# linear_supply2.net
KiCad netlist of a schematic drawn in EAGLE
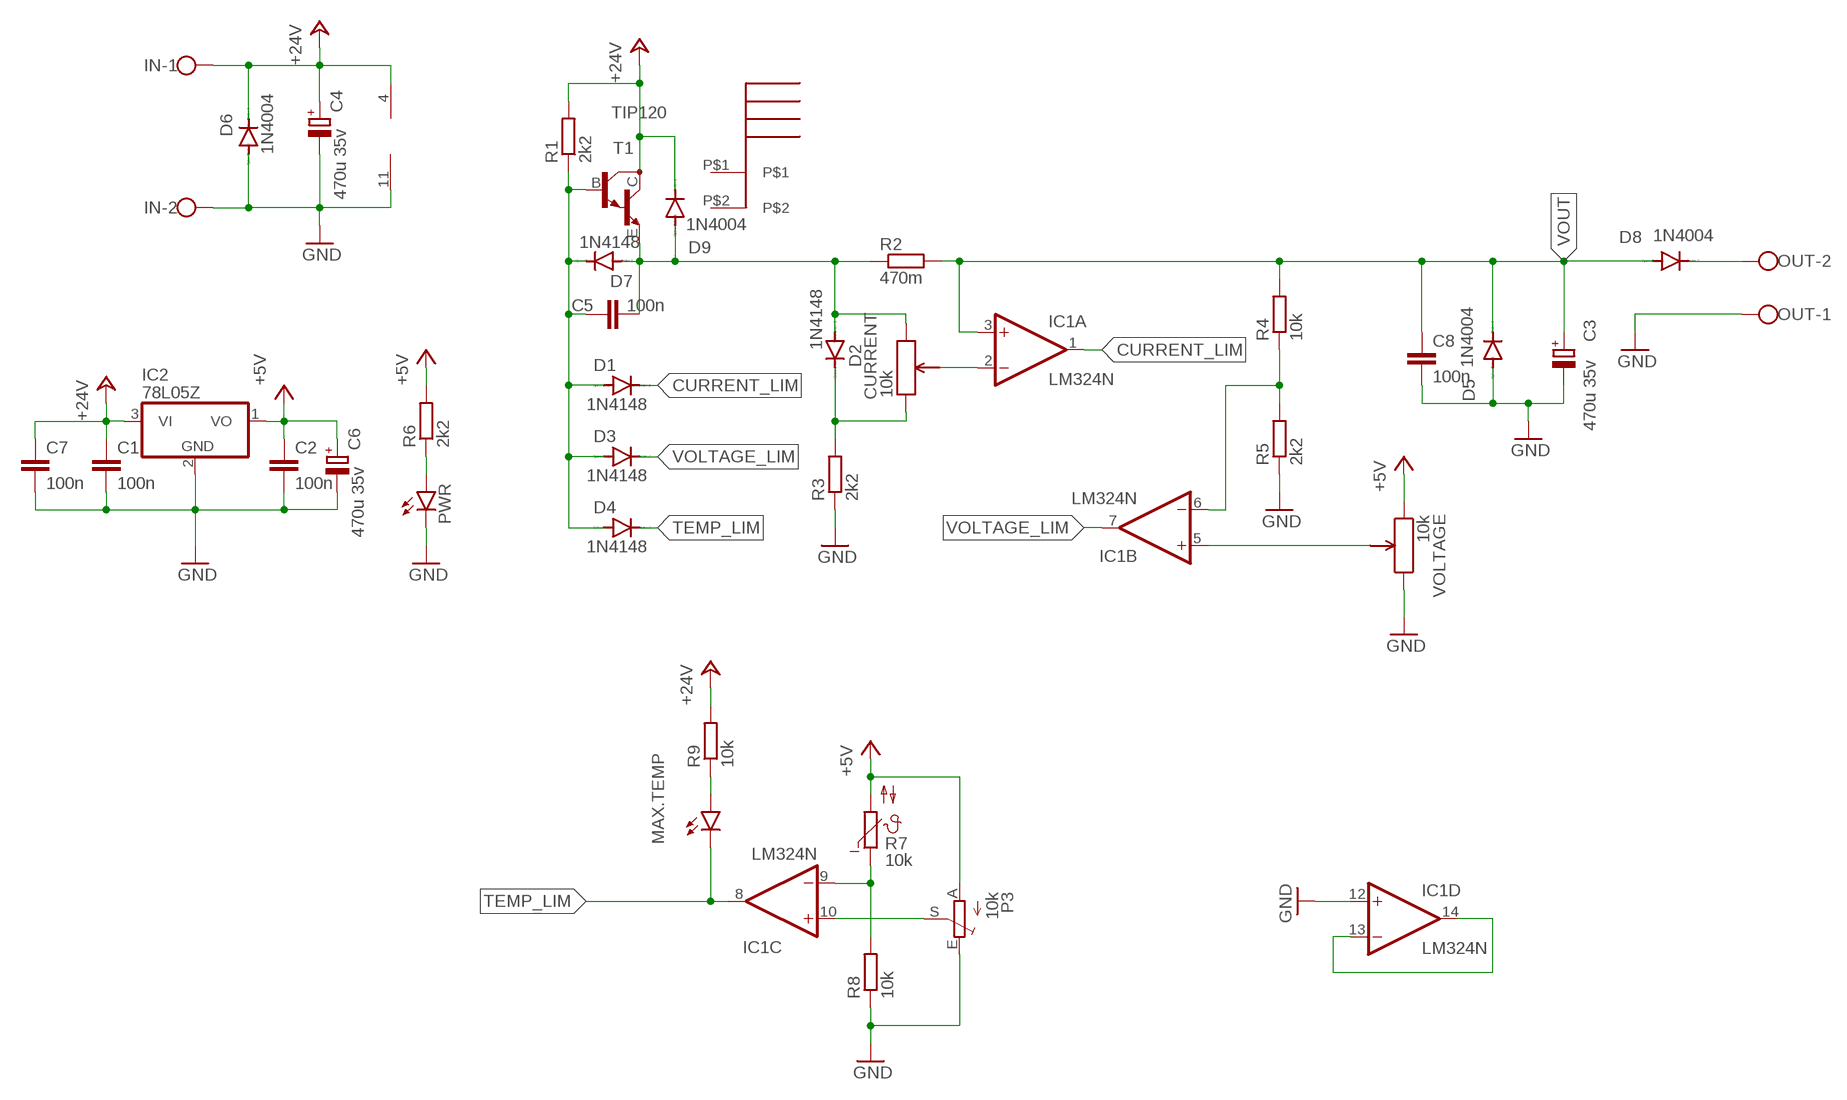
[diagram p0: schematic, sheet 1]

(export (version "E")
  (design (tool "Eeschema 10.0.6"))
  (components
    (comp (ref "C1")
      (value "100n")
      (footprint "eagle-import:C050-024X044")
      (libsource (lib "eagle-import") (part "C-EU050-024X044"))
    )
    (comp (ref "C2")
      (value "100n")
      (footprint "eagle-import:C050-024X044")
      (libsource (lib "eagle-import") (part "C-EU050-024X044"))
    )
    (comp (ref "C3")
      (value "470u 35v")
      (footprint "eagle-import:E5-10,5")
      (libsource (lib "eagle-import") (part "CPOL-EUE5-10.5"))
    )
    (comp (ref "C4")
      (value "470u 35v")
      (footprint "eagle-import:E5-10,5")
      (libsource (lib "eagle-import") (part "CPOL-EUE5-10.5"))
    )
    (comp (ref "C5")
      (value "100n")
      (footprint "eagle-import:C050-024X044")
      (libsource (lib "eagle-import") (part "C-EU050-024X044"))
    )
    (comp (ref "C6")
      (value "470u 35v")
      (footprint "eagle-import:E5-10,5")
      (libsource (lib "eagle-import") (part "CPOL-EUE5-10.5"))
    )
    (comp (ref "C7")
      (value "100n")
      (footprint "eagle-import:C1206K")
      (libsource (lib "eagle-import") (part "C-EUC1206K"))
    )
    (comp (ref "C8")
      (value "100n")
      (footprint "eagle-import:C050-050X075")
      (libsource (lib "eagle-import") (part "C-EU050-050X075"))
    )
    (comp (ref "CURRENT")
      (value "10k")
      (footprint "eagle-import:THRU_PCW_POT")
      (libsource (lib "eagle-import") (part "THRU_PCB_POTKASO1"))
    )
    (comp (ref "D1")
      (value "1N4148")
      (footprint "eagle-import:DO35-7")
      (libsource (lib "eagle-import") (part "1N4148DO35-7"))
    )
    (comp (ref "D2")
      (value "1N4148")
      (footprint "eagle-import:DO35-7")
      (libsource (lib "eagle-import") (part "1N4148DO35-7"))
    )
    (comp (ref "D3")
      (value "1N4148")
      (footprint "eagle-import:DO35-7")
      (libsource (lib "eagle-import") (part "1N4148DO35-7"))
    )
    (comp (ref "D4")
      (value "1N4148")
      (footprint "eagle-import:DO35-7")
      (libsource (lib "eagle-import") (part "1N4148DO35-7"))
    )
    (comp (ref "D5")
      (value "1N4004")
      (footprint "eagle-import:DO41-10")
      (libsource (lib "eagle-import") (part "1N4004"))
    )
    (comp (ref "D6")
      (value "1N4004")
      (footprint "eagle-import:DO41-10")
      (libsource (lib "eagle-import") (part "1N4004"))
    )
    (comp (ref "D7")
      (value "1N4148")
      (footprint "eagle-import:DO35-7")
      (libsource (lib "eagle-import") (part "1N4148DO35-7"))
    )
    (comp (ref "D8")
      (value "1N4004")
      (footprint "eagle-import:DO41-10")
      (libsource (lib "eagle-import") (part "1N4004"))
    )
    (comp (ref "D9")
      (value "1N4004")
      (footprint "eagle-import:DO41-10")
      (libsource (lib "eagle-import") (part "1N4004"))
    )
    (comp (ref "IC1")
      (value "LM324N")
      (footprint "eagle-import:DIL14")
      (libsource (lib "eagle-import") (part "LM324N"))
    )
    (comp (ref "IC2")
      (value "78L05Z")
      (footprint "eagle-import:TO92")
      (libsource (lib "eagle-import") (part "78ZL05"))
    )
    (comp (ref "IN")
      (value "W237-102")
      (footprint "eagle-import:W237-102")
      (fields (field (name "MPN") "237-102"))
      (libsource (lib "eagle-import") (part "W237-102"))
    )
    (comp (ref "MAX.TEMP")
      (value "LED3MM")
      (footprint "eagle-import:LED3MM")
      (libsource (lib "eagle-import") (part "LED3MM"))
    )
    (comp (ref "OUT")
      (value "W237-102")
      (footprint "eagle-import:W237-102")
      (fields (field (name "MPN") "237-102"))
      (libsource (lib "eagle-import") (part "W237-102"))
    )
    (comp (ref "P3")
      (value "10k")
      (footprint "eagle-import:CA6V")
      (libsource (lib "eagle-import") (part "TRIM_EU-CA6V"))
    )
    (comp (ref "PWR")
      (value "LED3MM")
      (footprint "eagle-import:LED3MM")
      (libsource (lib "eagle-import") (part "LED3MM"))
    )
    (comp (ref "R1")
      (value "2k2")
      (footprint "eagle-import:0207_10")
      (libsource (lib "eagle-import") (part "R-EU_0207/10"))
    )
    (comp (ref "R2")
      (value "470m")
      (footprint "eagle-import:0411_12")
      (libsource (lib "eagle-import") (part "R-EU_0411/12"))
    )
    (comp (ref "R3")
      (value "2k2")
      (footprint "eagle-import:0207_10")
      (libsource (lib "eagle-import") (part "R-EU_0207/10"))
    )
    (comp (ref "R4")
      (value "10k")
      (footprint "eagle-import:0207_10")
      (libsource (lib "eagle-import") (part "R-EU_0207/10"))
    )
    (comp (ref "R5")
      (value "2k2")
      (footprint "eagle-import:0207_10")
      (libsource (lib "eagle-import") (part "R-EU_0207/10"))
    )
    (comp (ref "R6")
      (value "2k2")
      (footprint "eagle-import:0207_10")
      (libsource (lib "eagle-import") (part "R-EU_0207/10"))
    )
    (comp (ref "R7")
      (value "10k")
      (footprint "eagle-import:P642")
      (libsource (lib "eagle-import") (part "V642"))
    )
    (comp (ref "R8")
      (value "10k")
      (footprint "eagle-import:0207_10")
      (libsource (lib "eagle-import") (part "R-EU_0207/10"))
    )
    (comp (ref "R9")
      (value "10k")
      (footprint "eagle-import:0207_10")
      (libsource (lib "eagle-import") (part "R-EU_0207/10"))
    )
    (comp (ref "T1")
      (value "TIP120")
      (footprint "eagle-import:SOT93")
      (libsource (lib "eagle-import") (part "BDV65"))
    )
    (comp (ref "U$1")
      (value "RAD-DY-KY/3")
      (footprint "eagle-import:RAD-DY-KY_3HEATSINK")
      (libsource (lib "eagle-import") (part "RAD-DY-KY/3"))
    )
    (comp (ref "VOLTAGE")
      (value "10k")
      (footprint "eagle-import:THRU_PCW_POT")
      (fields (field (name "SPICEPREFIX") "J"))
      (libsource (lib "eagle-import") (part "THRU_PCB_POTKASO1"))
    )
  )
  (nets
    (net (code "1") (name "+5V") (class "Default")
      (node (ref "C2") (pin "1") (pinfunction "1_1") (pintype "passive"))
      (node (ref "C6") (pin "+") (pinfunction "+_+") (pintype "passive"))
      (node (ref "IC2") (pin "1") (pinfunction "VO_1") (pintype "passive"))
      (node (ref "P3") (pin "A") (pinfunction "A_A") (pintype "passive"))
      (node (ref "R6") (pin "2") (pinfunction "2_2") (pintype "passive"))
      (node (ref "R7") (pin "2") (pinfunction "2_2") (pintype "passive"))
      (node (ref "VOLTAGE") (pin "P$1") (pinfunction "1_P$1") (pintype "bidirectional"))
    )
    (net (code "2") (name "+24V") (class "Default")
      (node (ref "C1") (pin "1") (pinfunction "1_1") (pintype "passive"))
      (node (ref "C4") (pin "+") (pinfunction "+_+") (pintype "passive"))
      (node (ref "C7") (pin "1") (pinfunction "1_1") (pintype "passive"))
      (node (ref "D6") (pin "C") (pinfunction "C_C") (pintype "passive"))
      (node (ref "D9") (pin "C") (pinfunction "C_C") (pintype "passive"))
      (node (ref "IC1") (pin "4") (pinfunction "V+_4") (pintype "power_in"))
      (node (ref "IC2") (pin "3") (pinfunction "VI_3") (pintype "input"))
      (node (ref "IN") (pin "1") (pinfunction "KL_1") (pintype "passive"))
      (node (ref "R1") (pin "2") (pinfunction "2_2") (pintype "passive"))
      (node (ref "R9") (pin "2") (pinfunction "2_2") (pintype "passive"))
      (node (ref "T1") (pin "C") (pinfunction "C_C") (pintype "passive"))
    )
    (net (code "3") (name "CURRENT_LIM") (class "Default")
      (node (ref "D1") (pin "C") (pinfunction "C_C") (pintype "passive"))
      (node (ref "IC1") (pin "1") (pinfunction "OUT_1") (pintype "output"))
    )
    (net (code "4") (name "GND") (class "Default")
      (node (ref "C1") (pin "2") (pinfunction "2_2") (pintype "passive"))
      (node (ref "C2") (pin "2") (pinfunction "2_2") (pintype "passive"))
      (node (ref "C3") (pin "-") (pinfunction "-_-") (pintype "passive"))
      (node (ref "C4") (pin "-") (pinfunction "-_-") (pintype "passive"))
      (node (ref "C6") (pin "-") (pinfunction "-_-") (pintype "passive"))
      (node (ref "C7") (pin "2") (pinfunction "2_2") (pintype "passive"))
      (node (ref "C8") (pin "2") (pinfunction "2_2") (pintype "passive"))
      (node (ref "D5") (pin "A") (pinfunction "A_A") (pintype "passive"))
      (node (ref "D6") (pin "A") (pinfunction "A_A") (pintype "passive"))
      (node (ref "IC1") (pin "11") (pinfunction "V-_11") (pintype "power_in"))
      (node (ref "IC1") (pin "12") (pinfunction "+IN_12") (pintype "input"))
      (node (ref "IC2") (pin "2") (pinfunction "GND_2") (pintype "passive"))
      (node (ref "IN") (pin "2") (pinfunction "KL_2") (pintype "passive"))
      (node (ref "OUT") (pin "1") (pinfunction "KL_1") (pintype "passive"))
      (node (ref "P3") (pin "E") (pinfunction "E_E") (pintype "passive"))
      (node (ref "PWR") (pin "K") (pinfunction "C_K") (pintype "passive"))
      (node (ref "R3") (pin "1") (pinfunction "1_1") (pintype "passive"))
      (node (ref "R5") (pin "1") (pinfunction "1_1") (pintype "passive"))
      (node (ref "R8") (pin "1") (pinfunction "1_1") (pintype "passive"))
      (node (ref "VOLTAGE") (pin "P$3") (pinfunction "3_P$3") (pintype "bidirectional"))
    )
    (net (code "5") (name "Net-(C5-Pad1)") (class "Default")
      (node (ref "C5") (pin "1") (pinfunction "1_1") (pintype "passive"))
      (node (ref "D1") (pin "A") (pinfunction "A_A") (pintype "passive"))
      (node (ref "D3") (pin "A") (pinfunction "A_A") (pintype "passive"))
      (node (ref "D4") (pin "A") (pinfunction "A_A") (pintype "passive"))
      (node (ref "D7") (pin "C") (pinfunction "C_C") (pintype "passive"))
      (node (ref "R1") (pin "1") (pinfunction "1_1") (pintype "passive"))
      (node (ref "T1") (pin "B") (pinfunction "B_B") (pintype "passive"))
    )
    (net (code "6") (name "Net-(CURRENT-1)") (class "Default")
      (node (ref "CURRENT") (pin "P$1") (pinfunction "1_P$1") (pintype "bidirectional"))
      (node (ref "D2") (pin "C") (pinfunction "C_C") (pintype "passive"))
      (node (ref "R3") (pin "2") (pinfunction "2_2") (pintype "passive"))
    )
    (net (code "7") (name "Net-(CURRENT-2)") (class "Default")
      (node (ref "CURRENT") (pin "P$2") (pinfunction "2_P$2") (pintype "bidirectional"))
      (node (ref "IC1") (pin "2") (pinfunction "-IN_2") (pintype "input"))
    )
    (net (code "8") (name "Net-(CURRENT-3)") (class "Default")
      (node (ref "C5") (pin "2") (pinfunction "2_2") (pintype "passive"))
      (node (ref "CURRENT") (pin "P$3") (pinfunction "3_P$3") (pintype "bidirectional"))
      (node (ref "D2") (pin "A") (pinfunction "A_A") (pintype "passive"))
      (node (ref "D7") (pin "A") (pinfunction "A_A") (pintype "passive"))
      (node (ref "D9") (pin "A") (pinfunction "A_A") (pintype "passive"))
      (node (ref "R2") (pin "1") (pinfunction "1_1") (pintype "passive"))
      (node (ref "T1") (pin "E") (pinfunction "E_E") (pintype "passive"))
    )
    (net (code "9") (name "Net-(IC1B-+IN)") (class "Default")
      (node (ref "IC1") (pin "5") (pinfunction "+IN_5") (pintype "input"))
      (node (ref "VOLTAGE") (pin "P$2") (pinfunction "2_P$2") (pintype "bidirectional"))
    )
    (net (code "10") (name "Net-(IC1B--IN)") (class "Default")
      (node (ref "IC1") (pin "6") (pinfunction "-IN_6") (pintype "input"))
      (node (ref "R4") (pin "1") (pinfunction "1_1") (pintype "passive"))
      (node (ref "R5") (pin "2") (pinfunction "2_2") (pintype "passive"))
    )
    (net (code "11") (name "Net-(IC1C-+IN)") (class "Default")
      (node (ref "IC1") (pin "10") (pinfunction "+IN_10") (pintype "input"))
      (node (ref "P3") (pin "S") (pinfunction "S_S") (pintype "passive"))
    )
    (net (code "12") (name "Net-(IC1C--IN)") (class "Default")
      (node (ref "IC1") (pin "9") (pinfunction "-IN_9") (pintype "input"))
      (node (ref "R7") (pin "1") (pinfunction "1_1") (pintype "passive"))
      (node (ref "R8") (pin "2") (pinfunction "2_2") (pintype "passive"))
    )
    (net (code "13") (name "Net-(IC1D--IN)") (class "Default")
      (node (ref "IC1") (pin "13") (pinfunction "-IN_13") (pintype "input"))
      (node (ref "IC1") (pin "14") (pinfunction "OUT_14") (pintype "output"))
    )
    (net (code "14") (name "Net-(MAX.TEMP-PadA)") (class "Default")
      (node (ref "MAX.TEMP") (pin "A") (pinfunction "A_A") (pintype "passive"))
      (node (ref "R9") (pin "1") (pinfunction "1_1") (pintype "passive"))
    )
    (net (code "15") (name "Net-(OUTB-KL)") (class "Default")
      (node (ref "D8") (pin "C") (pinfunction "C_C") (pintype "passive"))
      (node (ref "OUT") (pin "2") (pinfunction "KL_2") (pintype "passive"))
    )
    (net (code "16") (name "Net-(PWR-PadA)") (class "Default")
      (node (ref "PWR") (pin "A") (pinfunction "A_A") (pintype "passive"))
      (node (ref "R6") (pin "1") (pinfunction "1_1") (pintype "passive"))
    )
    (net (code "17") (name "TEMP_LIM") (class "Default")
      (node (ref "D4") (pin "C") (pinfunction "C_C") (pintype "passive"))
      (node (ref "IC1") (pin "8") (pinfunction "OUT_8") (pintype "output"))
      (node (ref "MAX.TEMP") (pin "K") (pinfunction "C_K") (pintype "passive"))
    )
    (net (code "18") (name "VOLTAGE_LIM") (class "Default")
      (node (ref "D3") (pin "C") (pinfunction "C_C") (pintype "passive"))
      (node (ref "IC1") (pin "7") (pinfunction "OUT_7") (pintype "output"))
    )
    (net (code "19") (name "VOUT") (class "Default")
      (node (ref "C3") (pin "+") (pinfunction "+_+") (pintype "passive"))
      (node (ref "C8") (pin "1") (pinfunction "1_1") (pintype "passive"))
      (node (ref "D5") (pin "C") (pinfunction "C_C") (pintype "passive"))
      (node (ref "D8") (pin "A") (pinfunction "A_A") (pintype "passive"))
      (node (ref "IC1") (pin "3") (pinfunction "+IN_3") (pintype "input"))
      (node (ref "R2") (pin "2") (pinfunction "2_2") (pintype "passive"))
      (node (ref "R4") (pin "2") (pinfunction "2_2") (pintype "passive"))
    )
    (net (code "20") (name "unconnected-(U$1-PadP$1)") (class "Default")
      (node (ref "U$1") (pin "P$1") (pinfunction "P$1_P$1") (pintype "bidirectional"))
    )
    (net (code "21") (name "unconnected-(U$1-PadP$2)") (class "Default")
      (node (ref "U$1") (pin "P$2") (pinfunction "P$2_P$2") (pintype "bidirectional"))
    )
  )
)
